# roco1044.net
KiCad netlist of a schematic drawn in EAGLE
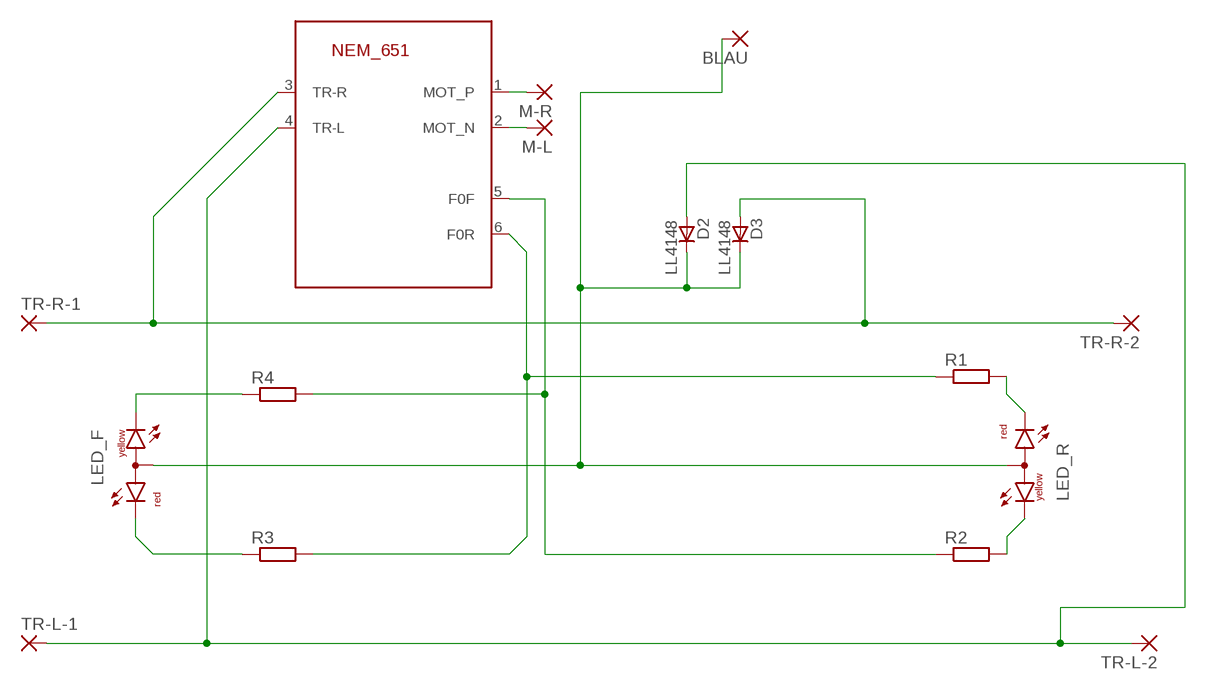
[diagram p0: schematic, sheet 1]

(export (version "E")
  (design (tool "Eeschema 10.0.6"))
  (components
    (comp (ref "651")
      (value "NEM_651-TS")
      (footprint "eagle-import:53047-06")
      (libsource (lib "eagle-import") (part "NEM_651-TS"))
    )
    (comp (ref "BLAU")
      (value "1,6/0,8")
      (footprint "eagle-import:1,6_0,8")
      (libsource (lib "eagle-import") (part "1,6/0,8"))
    )
    (comp (ref "D2")
      (value "LL4148")
      (footprint "eagle-import:SOD80_DO213AA_MINIMELF")
      (libsource (lib "eagle-import") (part "LL4148"))
    )
    (comp (ref "D3")
      (value "LL4148")
      (footprint "eagle-import:SOD80_DO213AA_MINIMELF")
      (libsource (lib "eagle-import") (part "LL4148"))
    )
    (comp (ref "LED_F")
      (value "DUOLED-RY-A")
      (footprint "eagle-import:DUOLED-A-5MM")
      (libsource (lib "eagle-import") (part "DUOLED-RY-A"))
    )
    (comp (ref "LED_R")
      (value "DUOLED-RY-A")
      (footprint "eagle-import:DUOLED-A-5MM")
      (libsource (lib "eagle-import") (part "DUOLED-RY-A"))
    )
    (comp (ref "M-L")
      (value "SMD5")
      (footprint "eagle-import:SMD2,54-5,08")
      (libsource (lib "eagle-import") (part "SMD5"))
    )
    (comp (ref "M-R")
      (value "SMD5")
      (footprint "eagle-import:SMD2,54-5,08")
      (libsource (lib "eagle-import") (part "SMD5"))
    )
    (comp (ref "R1")
      (value "R-EU_R1206")
      (footprint "eagle-import:R1206")
      (libsource (lib "eagle-import") (part "R-EU_R1206"))
    )
    (comp (ref "R2")
      (value "R-EU_R1206")
      (footprint "eagle-import:R1206")
      (libsource (lib "eagle-import") (part "R-EU_R1206"))
    )
    (comp (ref "R3")
      (value "R-EU_R1206")
      (footprint "eagle-import:R1206")
      (libsource (lib "eagle-import") (part "R-EU_R1206"))
    )
    (comp (ref "R4")
      (value "R-EU_R1206")
      (footprint "eagle-import:R1206")
      (libsource (lib "eagle-import") (part "R-EU_R1206"))
    )
    (comp (ref "TR-L-1")
      (value "SMD5")
      (footprint "eagle-import:SMD2,54-5,08")
      (libsource (lib "eagle-import") (part "SMD5"))
    )
    (comp (ref "TR-L-2")
      (value "SMD5")
      (footprint "eagle-import:SMD2,54-5,08")
      (libsource (lib "eagle-import") (part "SMD5"))
    )
    (comp (ref "TR-R-1")
      (value "SMD5")
      (footprint "eagle-import:SMD2,54-5,08")
      (libsource (lib "eagle-import") (part "SMD5"))
    )
    (comp (ref "TR-R-2")
      (value "SMD5")
      (footprint "eagle-import:SMD2,54-5,08")
      (libsource (lib "eagle-import") (part "SMD5"))
    )
  )
  (nets
    (net (code "1") (name "Net-(651-F0F)") (class "Default")
      (node (ref "651") (pin "5") (pinfunction "F0F_5") (pintype "bidirectional"))
      (node (ref "R2") (pin "1") (pinfunction "1_1") (pintype "passive"))
      (node (ref "R4") (pin "2") (pinfunction "2_2") (pintype "passive"))
    )
    (net (code "2") (name "Net-(651-F0R)") (class "Default")
      (node (ref "651") (pin "6") (pinfunction "F0R_6") (pintype "bidirectional"))
      (node (ref "R1") (pin "1") (pinfunction "1_1") (pintype "passive"))
      (node (ref "R3") (pin "2") (pinfunction "2_2") (pintype "passive"))
    )
    (net (code "3") (name "Net-(651-MOT_N)") (class "Default")
      (node (ref "651") (pin "2") (pinfunction "MOT_N_2") (pintype "bidirectional"))
      (node (ref "M-L") (pin "1") (pinfunction "P_1") (pintype "passive"))
    )
    (net (code "4") (name "Net-(651-MOT_P)") (class "Default")
      (node (ref "651") (pin "1") (pinfunction "MOT_P_1") (pintype "bidirectional"))
      (node (ref "M-R") (pin "1") (pinfunction "P_1") (pintype "passive"))
    )
    (net (code "5") (name "Net-(651-TR-L)") (class "Default")
      (node (ref "651") (pin "4") (pinfunction "TR-L_4") (pintype "bidirectional"))
      (node (ref "D2") (pin "A") (pinfunction "A_A") (pintype "passive"))
      (node (ref "TR-L-1") (pin "1") (pinfunction "P_1") (pintype "passive"))
      (node (ref "TR-L-2") (pin "1") (pinfunction "P_1") (pintype "passive"))
    )
    (net (code "6") (name "Net-(651-TR-R)") (class "Default")
      (node (ref "651") (pin "3") (pinfunction "TR-R_3") (pintype "bidirectional"))
      (node (ref "D3") (pin "A") (pinfunction "A_A") (pintype "passive"))
      (node (ref "TR-R-1") (pin "1") (pinfunction "P_1") (pintype "passive"))
      (node (ref "TR-R-2") (pin "1") (pinfunction "P_1") (pintype "passive"))
    )
    (net (code "7") (name "Net-(BLAU-P)") (class "Default")
      (node (ref "BLAU") (pin "1") (pinfunction "P_1") (pintype "passive"))
      (node (ref "D2") (pin "C") (pinfunction "C_C") (pintype "passive"))
      (node (ref "D3") (pin "C") (pinfunction "C_C") (pintype "passive"))
      (node (ref "LED_F") (pin "A") (pinfunction "A_A") (pintype "passive"))
      (node (ref "LED_R") (pin "A") (pinfunction "A_A") (pintype "passive"))
    )
    (net (code "8") (name "Net-(LED_F-CY)") (class "Default")
      (node (ref "LED_F") (pin "CX") (pinfunction "CY_CX") (pintype "passive"))
      (node (ref "R4") (pin "1") (pinfunction "1_1") (pintype "passive"))
    )
    (net (code "9") (name "Net-(LED_F-PadCR)") (class "Default")
      (node (ref "LED_F") (pin "CR") (pinfunction "CR_CR") (pintype "passive"))
      (node (ref "R3") (pin "1") (pinfunction "1_1") (pintype "passive"))
    )
    (net (code "10") (name "Net-(LED_R-CY)") (class "Default")
      (node (ref "LED_R") (pin "CX") (pinfunction "CY_CX") (pintype "passive"))
      (node (ref "R2") (pin "2") (pinfunction "2_2") (pintype "passive"))
    )
    (net (code "11") (name "Net-(LED_R-PadCR)") (class "Default")
      (node (ref "LED_R") (pin "CR") (pinfunction "CR_CR") (pintype "passive"))
      (node (ref "R1") (pin "2") (pinfunction "2_2") (pintype "passive"))
    )
  )
)
